# OBS-buttons-processor.net
KiCad netlist of a schematic drawn in EAGLE
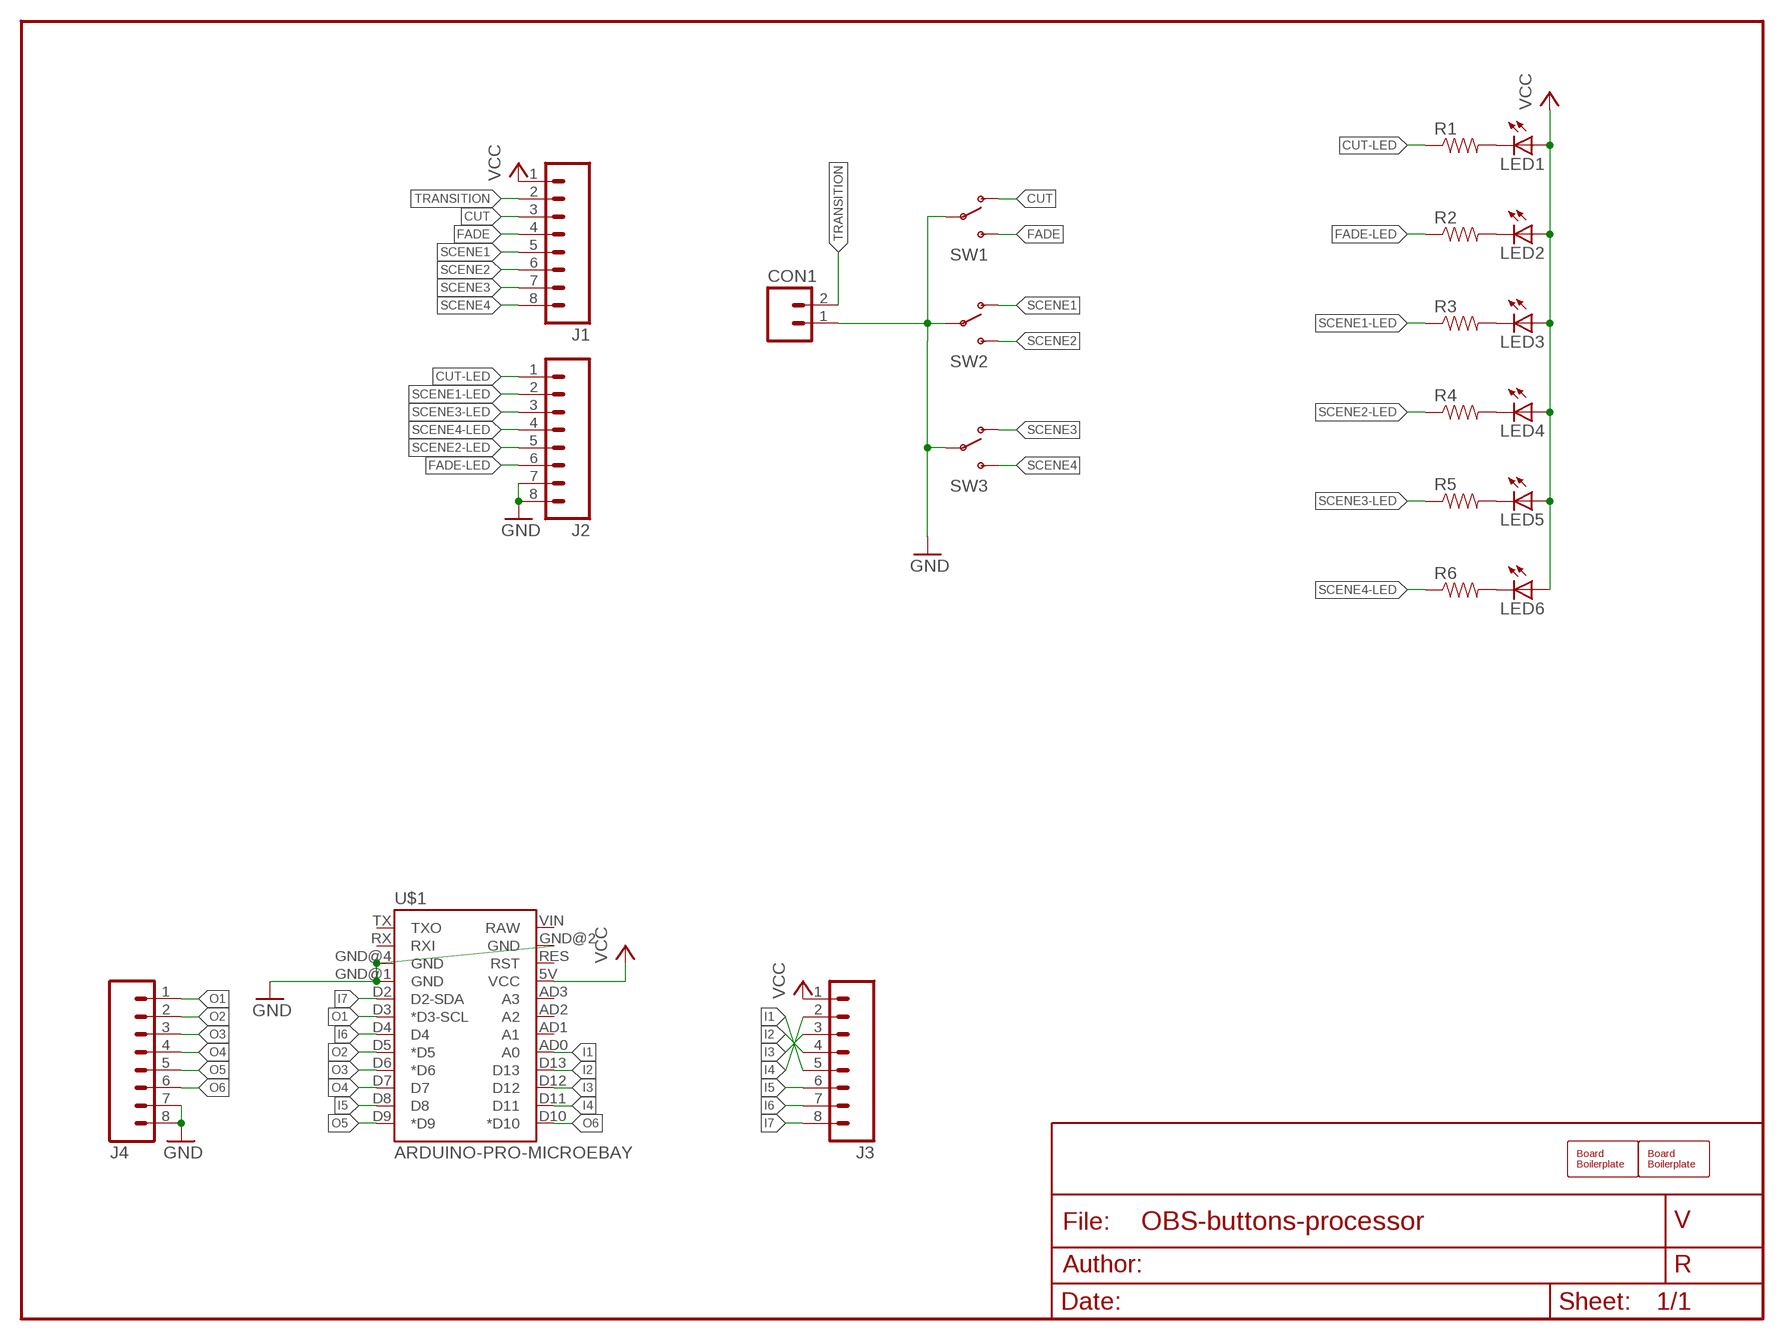
[diagram p0: schematic, sheet 1]

(export (version "E")
  (design (tool "Eeschema 10.0.6"))
  (components
    (comp (ref "BOARD1")
      (value "BOARD100X50-NOHOLES")
      (footprint "eagle-import:BOARD-SEEED10X5-NOHOLES")
      (libsource (lib "eagle-import") (part "BOARD100X50-NOHOLES"))
    )
    (comp (ref "BOARD2")
      (value "BOARD100X50-NOHOLES")
      (footprint "eagle-import:BOARD-SEEED10X5-NOHOLES")
      (libsource (lib "eagle-import") (part "BOARD100X50-NOHOLES"))
    )
    (comp (ref "CON1")
      (value "CONNECTOR-M02508-LOCK")
      (footprint "eagle-import:MSTB2")
      (libsource (lib "eagle-import") (part "CONNECTOR-M02508-LOCK"))
    )
    (comp (ref "J1")
      (value "CONNECTOR-M08LOCK")
      (footprint "eagle-import:1X08_LOCK")
      (libsource (lib "eagle-import") (part "CONNECTOR-M08LOCK"))
    )
    (comp (ref "J2")
      (value "CONNECTOR-M08LOCK")
      (footprint "eagle-import:1X08_LOCK")
      (libsource (lib "eagle-import") (part "CONNECTOR-M08LOCK"))
    )
    (comp (ref "J3")
      (value "CONNECTOR-M08LOCK")
      (footprint "eagle-import:1X08_LOCK")
      (libsource (lib "eagle-import") (part "CONNECTOR-M08LOCK"))
    )
    (comp (ref "J4")
      (value "CONNECTOR-M08LOCK")
      (footprint "eagle-import:1X08_LOCK")
      (libsource (lib "eagle-import") (part "CONNECTOR-M08LOCK"))
    )
    (comp (ref "LED1")
      (value "LEDLED5MM")
      (footprint "eagle-import:LED5MM")
      (libsource (lib "eagle-import") (part "LEDLED5MM"))
    )
    (comp (ref "LED2")
      (value "LEDLED5MM")
      (footprint "eagle-import:LED5MM")
      (libsource (lib "eagle-import") (part "LEDLED5MM"))
    )
    (comp (ref "LED3")
      (value "LEDLED5MM")
      (footprint "eagle-import:LED5MM")
      (libsource (lib "eagle-import") (part "LEDLED5MM"))
    )
    (comp (ref "LED4")
      (value "LEDLED5MM")
      (footprint "eagle-import:LED5MM")
      (libsource (lib "eagle-import") (part "LEDLED5MM"))
    )
    (comp (ref "LED5")
      (value "LEDLED5MM")
      (footprint "eagle-import:LED5MM")
      (libsource (lib "eagle-import") (part "LEDLED5MM"))
    )
    (comp (ref "LED6")
      (value "LEDLED5MM")
      (footprint "eagle-import:LED5MM")
      (libsource (lib "eagle-import") (part "LEDLED5MM"))
    )
    (comp (ref "R1")
      (value "RPTH04")
      (footprint "eagle-import:AXIAL-0.4-RES")
      (libsource (lib "eagle-import") (part "RPTH04"))
    )
    (comp (ref "R2")
      (value "RPTH04")
      (footprint "eagle-import:AXIAL-0.4-RES")
      (libsource (lib "eagle-import") (part "RPTH04"))
    )
    (comp (ref "R3")
      (value "RPTH04")
      (footprint "eagle-import:AXIAL-0.4-RES")
      (libsource (lib "eagle-import") (part "RPTH04"))
    )
    (comp (ref "R4")
      (value "RPTH04")
      (footprint "eagle-import:AXIAL-0.4-RES")
      (libsource (lib "eagle-import") (part "RPTH04"))
    )
    (comp (ref "R5")
      (value "RPTH04")
      (footprint "eagle-import:AXIAL-0.4-RES")
      (libsource (lib "eagle-import") (part "RPTH04"))
    )
    (comp (ref "R6")
      (value "RPTH04")
      (footprint "eagle-import:AXIAL-0.4-RES")
      (libsource (lib "eagle-import") (part "RPTH04"))
    )
    (comp (ref "SW1")
      (value "SWITCH-SPSTPTH-508")
      (footprint "eagle-import:SWITCH-SPDT-508")
      (libsource (lib "eagle-import") (part "SWITCH-SPSTPTH-508"))
    )
    (comp (ref "SW2")
      (value "SWITCH-SPSTPTH-508")
      (footprint "eagle-import:SWITCH-SPDT-508")
      (libsource (lib "eagle-import") (part "SWITCH-SPSTPTH-508"))
    )
    (comp (ref "SW3")
      (value "SWITCH-SPSTPTH-508")
      (footprint "eagle-import:SWITCH-SPDT-508")
      (libsource (lib "eagle-import") (part "SWITCH-SPSTPTH-508"))
    )
    (comp (ref "U$1")
      (value "ARDUINO-PRO-MICROEBAY")
      (footprint "eagle-import:ARDUINO-PRO-MICRO")
      (libsource (lib "eagle-import") (part "ARDUINO-PRO-MICROEBAY"))
    )
  )
  (nets
    (net (code "1") (name "CUT") (class "Default")
      (node (ref "J1") (pin "3") (pinfunction "3_3") (pintype "passive"))
      (node (ref "SW1") (pin "1") (pinfunction "O_1") (pintype "passive"))
    )
    (net (code "2") (name "CUT-LED") (class "Default")
      (node (ref "J2") (pin "1") (pinfunction "1_1") (pintype "passive"))
      (node (ref "R1") (pin "P$1") (pinfunction "1_P$1") (pintype "passive"))
    )
    (net (code "3") (name "FADE") (class "Default")
      (node (ref "J1") (pin "4") (pinfunction "4_4") (pintype "passive"))
      (node (ref "SW1") (pin "3") (pinfunction "S_3") (pintype "passive"))
    )
    (net (code "4") (name "FADE-LED") (class "Default")
      (node (ref "J2") (pin "6") (pinfunction "6_6") (pintype "passive"))
      (node (ref "R2") (pin "P$1") (pinfunction "1_P$1") (pintype "passive"))
    )
    (net (code "5") (name "GND") (class "Default")
      (node (ref "CON1") (pin "1") (pinfunction "A_1") (pintype "passive"))
      (node (ref "J2") (pin "7") (pinfunction "7_7") (pintype "passive"))
      (node (ref "J2") (pin "8") (pinfunction "8_8") (pintype "passive"))
      (node (ref "J4") (pin "7") (pinfunction "7_7") (pintype "passive"))
      (node (ref "J4") (pin "8") (pinfunction "8_8") (pintype "passive"))
      (node (ref "SW1") (pin "2") (pinfunction "P_2") (pintype "passive"))
      (node (ref "SW2") (pin "2") (pinfunction "P_2") (pintype "passive"))
      (node (ref "SW3") (pin "2") (pinfunction "P_2") (pintype "passive"))
      (node (ref "U$1") (pin "GND@1") (pinfunction "GND_GND@1") (pintype "bidirectional"))
      (node (ref "U$1") (pin "GND@2") (pinfunction "GND_GND@2") (pintype "bidirectional"))
      (node (ref "U$1") (pin "GND@4") (pinfunction "GND_GND@4") (pintype "bidirectional"))
    )
    (net (code "6") (name "I1") (class "Default")
      (node (ref "J3") (pin "5") (pinfunction "5_5") (pintype "passive"))
      (node (ref "U$1") (pin "AD0") (pinfunction "A0_AD0") (pintype "bidirectional"))
    )
    (net (code "7") (name "I2") (class "Default")
      (node (ref "J3") (pin "4") (pinfunction "4_4") (pintype "passive"))
      (node (ref "U$1") (pin "D13") (pinfunction "D13_D13") (pintype "bidirectional"))
    )
    (net (code "8") (name "I3") (class "Default")
      (node (ref "J3") (pin "3") (pinfunction "3_3") (pintype "passive"))
      (node (ref "U$1") (pin "D12") (pinfunction "D12_D12") (pintype "bidirectional"))
    )
    (net (code "9") (name "I4") (class "Default")
      (node (ref "J3") (pin "2") (pinfunction "2_2") (pintype "passive"))
      (node (ref "U$1") (pin "D11") (pinfunction "D11_D11") (pintype "bidirectional"))
    )
    (net (code "10") (name "I5") (class "Default")
      (node (ref "J3") (pin "6") (pinfunction "6_6") (pintype "passive"))
      (node (ref "U$1") (pin "D8") (pinfunction "D8_D8") (pintype "bidirectional"))
    )
    (net (code "11") (name "I6") (class "Default")
      (node (ref "J3") (pin "7") (pinfunction "7_7") (pintype "passive"))
      (node (ref "U$1") (pin "D4") (pinfunction "D4_D4") (pintype "bidirectional"))
    )
    (net (code "12") (name "I7") (class "Default")
      (node (ref "J3") (pin "8") (pinfunction "8_8") (pintype "passive"))
      (node (ref "U$1") (pin "D2") (pinfunction "D2-SDA_D2") (pintype "bidirectional"))
    )
    (net (code "13") (name "Net-(LED1-C)") (class "Default")
      (node (ref "LED1") (pin "K") (pinfunction "C_K") (pintype "passive"))
      (node (ref "R1") (pin "P$2") (pinfunction "2_P$2") (pintype "passive"))
    )
    (net (code "14") (name "Net-(LED2-C)") (class "Default")
      (node (ref "LED2") (pin "K") (pinfunction "C_K") (pintype "passive"))
      (node (ref "R2") (pin "P$2") (pinfunction "2_P$2") (pintype "passive"))
    )
    (net (code "15") (name "Net-(LED3-C)") (class "Default")
      (node (ref "LED3") (pin "K") (pinfunction "C_K") (pintype "passive"))
      (node (ref "R3") (pin "P$2") (pinfunction "2_P$2") (pintype "passive"))
    )
    (net (code "16") (name "Net-(LED4-C)") (class "Default")
      (node (ref "LED4") (pin "K") (pinfunction "C_K") (pintype "passive"))
      (node (ref "R4") (pin "P$2") (pinfunction "2_P$2") (pintype "passive"))
    )
    (net (code "17") (name "Net-(LED5-C)") (class "Default")
      (node (ref "LED5") (pin "K") (pinfunction "C_K") (pintype "passive"))
      (node (ref "R5") (pin "P$2") (pinfunction "2_P$2") (pintype "passive"))
    )
    (net (code "18") (name "Net-(LED6-C)") (class "Default")
      (node (ref "LED6") (pin "K") (pinfunction "C_K") (pintype "passive"))
      (node (ref "R6") (pin "P$2") (pinfunction "2_P$2") (pintype "passive"))
    )
    (net (code "19") (name "O1") (class "Default")
      (node (ref "J4") (pin "1") (pinfunction "1_1") (pintype "passive"))
      (node (ref "U$1") (pin "D3") (pinfunction "*D3-SCL_D3") (pintype "bidirectional"))
    )
    (net (code "20") (name "O2") (class "Default")
      (node (ref "J4") (pin "2") (pinfunction "2_2") (pintype "passive"))
      (node (ref "U$1") (pin "D5") (pinfunction "*D5_D5") (pintype "bidirectional"))
    )
    (net (code "21") (name "O3") (class "Default")
      (node (ref "J4") (pin "3") (pinfunction "3_3") (pintype "passive"))
      (node (ref "U$1") (pin "D6") (pinfunction "*D6_D6") (pintype "bidirectional"))
    )
    (net (code "22") (name "O4") (class "Default")
      (node (ref "J4") (pin "4") (pinfunction "4_4") (pintype "passive"))
      (node (ref "U$1") (pin "D7") (pinfunction "D7_D7") (pintype "bidirectional"))
    )
    (net (code "23") (name "O5") (class "Default")
      (node (ref "J4") (pin "5") (pinfunction "5_5") (pintype "passive"))
      (node (ref "U$1") (pin "D9") (pinfunction "*D9_D9") (pintype "bidirectional"))
    )
    (net (code "24") (name "O6") (class "Default")
      (node (ref "J4") (pin "6") (pinfunction "6_6") (pintype "passive"))
      (node (ref "U$1") (pin "D10") (pinfunction "*D10_D10") (pintype "bidirectional"))
    )
    (net (code "25") (name "SCENE1") (class "Default")
      (node (ref "J1") (pin "5") (pinfunction "5_5") (pintype "passive"))
      (node (ref "SW2") (pin "1") (pinfunction "O_1") (pintype "passive"))
    )
    (net (code "26") (name "SCENE1-LED") (class "Default")
      (node (ref "J2") (pin "2") (pinfunction "2_2") (pintype "passive"))
      (node (ref "R3") (pin "P$1") (pinfunction "1_P$1") (pintype "passive"))
    )
    (net (code "27") (name "SCENE2") (class "Default")
      (node (ref "J1") (pin "6") (pinfunction "6_6") (pintype "passive"))
      (node (ref "SW2") (pin "3") (pinfunction "S_3") (pintype "passive"))
    )
    (net (code "28") (name "SCENE2-LED") (class "Default")
      (node (ref "J2") (pin "5") (pinfunction "5_5") (pintype "passive"))
      (node (ref "R4") (pin "P$1") (pinfunction "1_P$1") (pintype "passive"))
    )
    (net (code "29") (name "SCENE3") (class "Default")
      (node (ref "J1") (pin "7") (pinfunction "7_7") (pintype "passive"))
      (node (ref "SW3") (pin "1") (pinfunction "O_1") (pintype "passive"))
    )
    (net (code "30") (name "SCENE3-LED") (class "Default")
      (node (ref "J2") (pin "3") (pinfunction "3_3") (pintype "passive"))
      (node (ref "R5") (pin "P$1") (pinfunction "1_P$1") (pintype "passive"))
    )
    (net (code "31") (name "SCENE4") (class "Default")
      (node (ref "J1") (pin "8") (pinfunction "8_8") (pintype "passive"))
      (node (ref "SW3") (pin "3") (pinfunction "S_3") (pintype "passive"))
    )
    (net (code "32") (name "SCENE4-LED") (class "Default")
      (node (ref "J2") (pin "4") (pinfunction "4_4") (pintype "passive"))
      (node (ref "R6") (pin "P$1") (pinfunction "1_P$1") (pintype "passive"))
    )
    (net (code "33") (name "TRANSITION") (class "Default")
      (node (ref "CON1") (pin "2") (pinfunction "B_2") (pintype "passive"))
      (node (ref "J1") (pin "2") (pinfunction "2_2") (pintype "passive"))
    )
    (net (code "34") (name "VCC") (class "Default")
      (node (ref "J1") (pin "1") (pinfunction "1_1") (pintype "passive"))
      (node (ref "J3") (pin "1") (pinfunction "1_1") (pintype "passive"))
      (node (ref "LED1") (pin "A") (pinfunction "A_A") (pintype "passive"))
      (node (ref "LED2") (pin "A") (pinfunction "A_A") (pintype "passive"))
      (node (ref "LED3") (pin "A") (pinfunction "A_A") (pintype "passive"))
      (node (ref "LED4") (pin "A") (pinfunction "A_A") (pintype "passive"))
      (node (ref "LED5") (pin "A") (pinfunction "A_A") (pintype "passive"))
      (node (ref "LED6") (pin "A") (pinfunction "A_A") (pintype "passive"))
      (node (ref "U$1") (pin "5V") (pinfunction "VCC_5V") (pintype "bidirectional"))
    )
    (net (code "35") (name "unconnected-(U$1-A1-PadAD1)") (class "Default")
      (node (ref "U$1") (pin "AD1") (pinfunction "A1_AD1") (pintype "bidirectional"))
    )
    (net (code "36") (name "unconnected-(U$1-A2-PadAD2)") (class "Default")
      (node (ref "U$1") (pin "AD2") (pinfunction "A2_AD2") (pintype "bidirectional"))
    )
    (net (code "37") (name "unconnected-(U$1-A3-PadAD3)") (class "Default")
      (node (ref "U$1") (pin "AD3") (pinfunction "A3_AD3") (pintype "bidirectional"))
    )
    (net (code "38") (name "unconnected-(U$1-RAW-PadVIN)") (class "Default")
      (node (ref "U$1") (pin "VIN") (pinfunction "RAW_VIN") (pintype "bidirectional"))
    )
    (net (code "39") (name "unconnected-(U$1-RST-PadRES)") (class "Default")
      (node (ref "U$1") (pin "RES") (pinfunction "RST_RES") (pintype "bidirectional"))
    )
    (net (code "40") (name "unconnected-(U$1-RXI-PadRX)") (class "Default")
      (node (ref "U$1") (pin "RX") (pinfunction "RXI_RX") (pintype "bidirectional"))
    )
    (net (code "41") (name "unconnected-(U$1-TXO-PadTX)") (class "Default")
      (node (ref "U$1") (pin "TX") (pinfunction "TXO_TX") (pintype "bidirectional"))
    )
  )
)
